# TC4plus.net
KiCad netlist of a schematic drawn in EAGLE
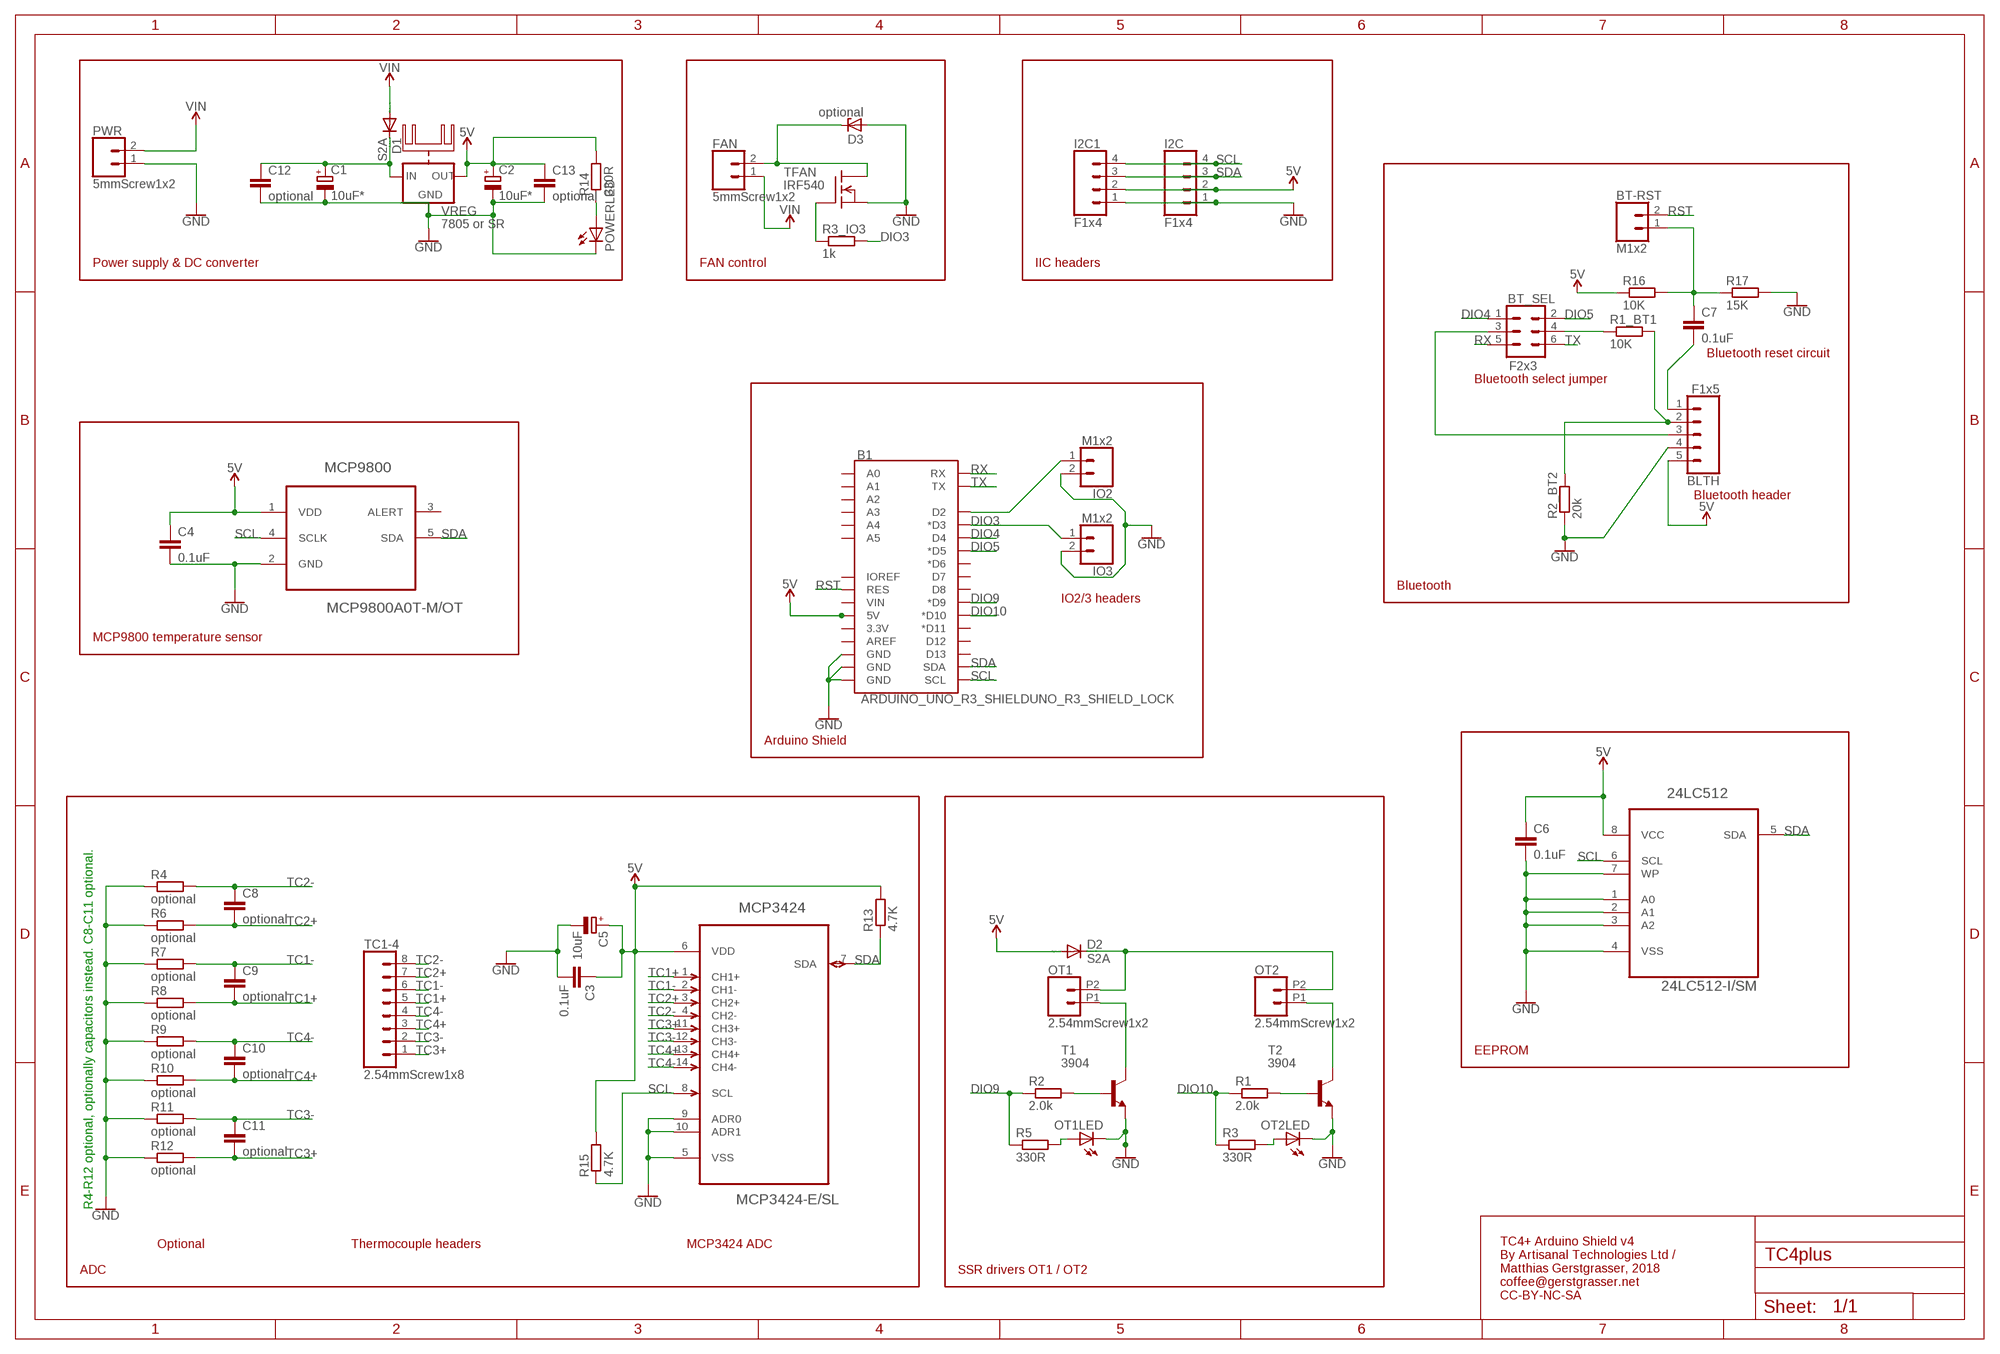
[diagram p0: schematic, sheet 1]

(export (version "E")
  (design (tool "Eeschema 10.0.6"))
  (components
    (comp (ref "24LC512")
      (value "24LC512-I/SM")
      (footprint "eagle-import:SOIC127P794X203-8N")
      (libsource (lib "eagle-import") (part "24LC512-I/SM"))
    )
    (comp (ref "B1")
      (value "ARDUINO_UNO_R3_SHIELDUNO_R3_SHIELD_LOCK")
      (footprint "eagle-import:UNO_R3_SHIELD_LOCK")
      (libsource (lib "eagle-import") (part "ARDUINO_UNO_R3_SHIELDUNO_R3_SHIELD_LOCK"))
    )
    (comp (ref "BLTH")
      (value "F1x5")
      (footprint "eagle-import:1X05_LOCK")
      (libsource (lib "eagle-import") (part "CONN_05LOCK"))
    )
    (comp (ref "BT-RST")
      (value "M1x2")
      (footprint "eagle-import:1X02")
      (libsource (lib "eagle-import") (part "CONN_02"))
    )
    (comp (ref "BT_SEL")
      (value "F2x3")
      (footprint "eagle-import:2X3")
      (libsource (lib "eagle-import") (part "CONN_03X2FEMALE"))
    )
    (comp (ref "C1")
      (value "10uF*")
      (footprint "eagle-import:E2-5")
      (libsource (lib "eagle-import") (part "CPOL-EUE2-5"))
    )
    (comp (ref "C2")
      (value "10uF*")
      (footprint "eagle-import:E2-5")
      (libsource (lib "eagle-import") (part "CPOL-EUE2-5"))
    )
    (comp (ref "C3")
      (value "0.1uF")
      (footprint "eagle-import:C0603")
      (libsource (lib "eagle-import") (part "C-EUC0603"))
    )
    (comp (ref "C4")
      (value "0.1uF")
      (footprint "eagle-import:C0603")
      (libsource (lib "eagle-import") (part "C-EUC0603"))
    )
    (comp (ref "C5")
      (value "10uF")
      (footprint "eagle-import:A_3216-18R")
      (libsource (lib "eagle-import") (part "CPOL-EUA/3216-18R"))
    )
    (comp (ref "C6")
      (value "0.1uF")
      (footprint "eagle-import:C0603")
      (libsource (lib "eagle-import") (part "C-EUC0603"))
    )
    (comp (ref "C7")
      (value "0.1uF")
      (footprint "eagle-import:C0603")
      (libsource (lib "eagle-import") (part "C-EUC0603"))
    )
    (comp (ref "C8")
      (value "optional")
      (footprint "eagle-import:C0603")
      (libsource (lib "eagle-import") (part "C-EUC0603"))
    )
    (comp (ref "C9")
      (value "optional")
      (footprint "eagle-import:C0603")
      (libsource (lib "eagle-import") (part "C-EUC0603"))
    )
    (comp (ref "C10")
      (value "optional")
      (footprint "eagle-import:C0603")
      (libsource (lib "eagle-import") (part "C-EUC0603"))
    )
    (comp (ref "C11")
      (value "optional")
      (footprint "eagle-import:C0603")
      (libsource (lib "eagle-import") (part "C-EUC0603"))
    )
    (comp (ref "C12")
      (value "optional")
      (footprint "eagle-import:C025-025X050")
      (libsource (lib "eagle-import") (part "C-EU025-025X050"))
    )
    (comp (ref "C13")
      (value "optional")
      (footprint "eagle-import:C025-025X050")
      (libsource (lib "eagle-import") (part "C-EU025-025X050"))
    )
    (comp (ref "D1")
      (value "S2A")
      (footprint "eagle-import:DO214AA")
      (libsource (lib "eagle-import") (part "DIODE-DO214AA"))
    )
    (comp (ref "D2")
      (value "S2A")
      (footprint "eagle-import:DO214AA")
      (libsource (lib "eagle-import") (part "DIODE-DO214AA"))
    )
    (comp (ref "D3")
      (value "optional")
      (footprint "eagle-import:SMB")
      (libsource (lib "eagle-import") (part "ZENER-DIODESMB"))
    )
    (comp (ref "FAN")
      (value "5mmScrew1x2")
      (footprint "eagle-import:SCREWTERMINAL-5MM-2")
      (libsource (lib "eagle-import") (part "SparkFun-Connectors_513_CONN_025MM"))
    )
    (comp (ref "I2C")
      (value "F1x4")
      (footprint "eagle-import:1X04_LOCK")
      (libsource (lib "eagle-import") (part "CONN_04LOCK"))
    )
    (comp (ref "I2C1")
      (value "F1x4")
      (footprint "eagle-import:1X04_LOCK")
      (libsource (lib "eagle-import") (part "CONN_04LOCK"))
    )
    (comp (ref "IO2")
      (value "M1x2")
      (footprint "eagle-import:1X02")
      (libsource (lib "eagle-import") (part "CONN_02"))
    )
    (comp (ref "IO3")
      (value "M1x2")
      (footprint "eagle-import:1X02")
      (libsource (lib "eagle-import") (part "CONN_02"))
    )
    (comp (ref "MCP3424")
      (value "MCP3424-E/SL")
      (footprint "eagle-import:SOIC127P600X175-14N")
      (libsource (lib "eagle-import") (part "MCP3424-E/SL"))
    )
    (comp (ref "MCP9800")
      (value "MCP9800A0T-M/OT")
      (footprint "eagle-import:SOT95P280X145-5N")
      (libsource (lib "eagle-import") (part "MCP9800A0T-M/OT"))
    )
    (comp (ref "OT1")
      (value "2.54mmScrew1x2")
      (footprint "eagle-import:1X02_2.54_SCREWTERM")
      (libsource (lib "eagle-import") (part "SparkFun-Connectors_513_CONN_022.54MM_SCREWTERM"))
    )
    (comp (ref "OT1LED")
      (value "LEDCHIP-LED0603")
      (footprint "eagle-import:CHIP-LED0603")
      (libsource (lib "eagle-import") (part "LEDCHIP-LED0603"))
    )
    (comp (ref "OT2")
      (value "2.54mmScrew1x2")
      (footprint "eagle-import:1X02_2.54_SCREWTERM")
      (libsource (lib "eagle-import") (part "SparkFun-Connectors_513_CONN_022.54MM_SCREWTERM"))
    )
    (comp (ref "OT2LED")
      (value "LEDCHIP-LED0603")
      (footprint "eagle-import:CHIP-LED0603")
      (libsource (lib "eagle-import") (part "LEDCHIP-LED0603"))
    )
    (comp (ref "POWERLED")
      (value "LEDCHIP-LED0603")
      (footprint "eagle-import:CHIP-LED0603")
      (libsource (lib "eagle-import") (part "LEDCHIP-LED0603"))
    )
    (comp (ref "PWR")
      (value "5mmScrew1x2")
      (footprint "eagle-import:SCREWTERMINAL-5MM-2")
      (libsource (lib "eagle-import") (part "SparkFun-Connectors_513_CONN_025MM"))
    )
    (comp (ref "R1")
      (value "2.0k")
      (footprint "eagle-import:R0603")
      (libsource (lib "eagle-import") (part "R-EU_R0603"))
    )
    (comp (ref "R1_BT1")
      (value "10K")
      (footprint "eagle-import:R0603")
      (libsource (lib "eagle-import") (part "R-EU_R0603"))
    )
    (comp (ref "R2")
      (value "2.0k")
      (footprint "eagle-import:R0603")
      (libsource (lib "eagle-import") (part "R-EU_R0603"))
    )
    (comp (ref "R2_BT2")
      (value "20k")
      (footprint "eagle-import:R0603")
      (libsource (lib "eagle-import") (part "R-EU_R0603"))
    )
    (comp (ref "R3")
      (value "330R")
      (footprint "eagle-import:R0603")
      (libsource (lib "eagle-import") (part "R-EU_R0603"))
    )
    (comp (ref "R3_IO3")
      (value "1k")
      (footprint "eagle-import:R0603")
      (libsource (lib "eagle-import") (part "R-EU_R0603"))
    )
    (comp (ref "R4")
      (value "optional")
      (footprint "eagle-import:R0603")
      (libsource (lib "eagle-import") (part "R-EU_R0603"))
    )
    (comp (ref "R5")
      (value "330R")
      (footprint "eagle-import:R0603")
      (libsource (lib "eagle-import") (part "R-EU_R0603"))
    )
    (comp (ref "R6")
      (value "optional")
      (footprint "eagle-import:R0603")
      (libsource (lib "eagle-import") (part "R-EU_R0603"))
    )
    (comp (ref "R7")
      (value "optional")
      (footprint "eagle-import:R0603")
      (libsource (lib "eagle-import") (part "R-EU_R0603"))
    )
    (comp (ref "R8")
      (value "optional")
      (footprint "eagle-import:R0603")
      (libsource (lib "eagle-import") (part "R-EU_R0603"))
    )
    (comp (ref "R9")
      (value "optional")
      (footprint "eagle-import:R0603")
      (libsource (lib "eagle-import") (part "R-EU_R0603"))
    )
    (comp (ref "R10")
      (value "optional")
      (footprint "eagle-import:R0603")
      (libsource (lib "eagle-import") (part "R-EU_R0603"))
    )
    (comp (ref "R11")
      (value "optional")
      (footprint "eagle-import:R0603")
      (libsource (lib "eagle-import") (part "R-EU_R0603"))
    )
    (comp (ref "R12")
      (value "optional")
      (footprint "eagle-import:R0603")
      (libsource (lib "eagle-import") (part "R-EU_R0603"))
    )
    (comp (ref "R13")
      (value "4.7K")
      (footprint "eagle-import:R0603")
      (libsource (lib "eagle-import") (part "R-EU_R0603"))
    )
    (comp (ref "R14")
      (value "330R")
      (footprint "eagle-import:R0603")
      (libsource (lib "eagle-import") (part "R-EU_R0603"))
    )
    (comp (ref "R15")
      (value "4.7K")
      (footprint "eagle-import:R0603")
      (libsource (lib "eagle-import") (part "R-EU_R0603"))
    )
    (comp (ref "R16")
      (value "10K")
      (footprint "eagle-import:R0603")
      (libsource (lib "eagle-import") (part "R-EU_R0603"))
    )
    (comp (ref "R17")
      (value "15K")
      (footprint "eagle-import:R0603")
      (libsource (lib "eagle-import") (part "R-EU_R0603"))
    )
    (comp (ref "T1")
      (value "3904")
      (footprint "eagle-import:SOT23-BEC")
      (libsource (lib "eagle-import") (part "-NPN-SOT23-BECMMBT3904LT1"))
    )
    (comp (ref "T2")
      (value "3904")
      (footprint "eagle-import:SOT23-BEC")
      (libsource (lib "eagle-import") (part "-NPN-SOT23-BECMMBT3904LT1"))
    )
    (comp (ref "TC1-4")
      (value "2.54mmScrew1x8")
      (footprint "eagle-import:1X08")
      (libsource (lib "eagle-import") (part "CONN_08{dblquote}"))
    )
    (comp (ref "TFAN")
      (value "IRF540")
      (footprint "eagle-import:TO220")
      (libsource (lib "eagle-import") (part "IRF540"))
    )
    (comp (ref "VREG")
      (value "7805 or SR")
      (footprint "eagle-import:78XXH")
      (libsource (lib "eagle-import") (part "78XXH"))
    )
  )
  (nets
    (net (code "1") (name "/DIO3") (class "Default")
      (node (ref "B1") (pin "D3") (pinfunction "*D3_D3") (pintype "bidirectional"))
      (node (ref "IO3") (pin "1") (pinfunction "1_1") (pintype "passive"))
      (node (ref "R3_IO3") (pin "2") (pinfunction "2_2") (pintype "passive"))
    )
    (net (code "2") (name "/DIO4") (class "Default")
      (node (ref "B1") (pin "D4") (pinfunction "D4_D4") (pintype "bidirectional"))
      (node (ref "BT_SEL") (pin "1") (pinfunction "1_1") (pintype "bidirectional"))
    )
    (net (code "3") (name "/DIO5") (class "Default")
      (node (ref "B1") (pin "D5") (pinfunction "*D5_D5") (pintype "bidirectional"))
      (node (ref "BT_SEL") (pin "2") (pinfunction "2_2") (pintype "bidirectional"))
    )
    (net (code "4") (name "/DIO9") (class "Default")
      (node (ref "B1") (pin "D9") (pinfunction "*D9_D9") (pintype "bidirectional"))
      (node (ref "R2") (pin "1") (pinfunction "1_1") (pintype "passive"))
      (node (ref "R5") (pin "1") (pinfunction "1_1") (pintype "passive"))
    )
    (net (code "5") (name "/DIO10") (class "Default")
      (node (ref "B1") (pin "D10") (pinfunction "*D10_D10") (pintype "bidirectional"))
      (node (ref "R1") (pin "1") (pinfunction "1_1") (pintype "passive"))
      (node (ref "R3") (pin "1") (pinfunction "1_1") (pintype "passive"))
    )
    (net (code "6") (name "/RST") (class "Default")
      (node (ref "B1") (pin "RES") (pinfunction "RES_RES") (pintype "bidirectional"))
      (node (ref "BT-RST") (pin "2") (pinfunction "2_2") (pintype "passive"))
    )
    (net (code "7") (name "/RX") (class "Default")
      (node (ref "B1") (pin "RX") (pinfunction "RX_RX") (pintype "bidirectional"))
      (node (ref "BT_SEL") (pin "5") (pinfunction "5_5") (pintype "bidirectional"))
    )
    (net (code "8") (name "/SCL") (class "Default")
      (node (ref "24LC512") (pin "6") (pinfunction "SCL_6") (pintype "input"))
      (node (ref "B1") (pin "SCL") (pinfunction "SCL_SCL") (pintype "bidirectional"))
      (node (ref "I2C") (pin "4") (pinfunction "4_4") (pintype "passive"))
      (node (ref "I2C1") (pin "4") (pinfunction "4_4") (pintype "passive"))
      (node (ref "MCP3424") (pin "8") (pinfunction "SCL_8") (pintype "input"))
      (node (ref "MCP9800") (pin "4") (pinfunction "SCLK_4") (pintype "input"))
      (node (ref "R15") (pin "1") (pinfunction "1_1") (pintype "passive"))
    )
    (net (code "9") (name "/SDA") (class "Default")
      (node (ref "24LC512") (pin "5") (pinfunction "SDA_5") (pintype "bidirectional"))
      (node (ref "B1") (pin "SDA") (pinfunction "SDA_SDA") (pintype "bidirectional"))
      (node (ref "I2C") (pin "3") (pinfunction "3_3") (pintype "passive"))
      (node (ref "I2C1") (pin "3") (pinfunction "3_3") (pintype "passive"))
      (node (ref "MCP3424") (pin "7") (pinfunction "SDA_7") (pintype "bidirectional"))
      (node (ref "MCP9800") (pin "5") (pinfunction "SDA_5") (pintype "bidirectional"))
      (node (ref "R13") (pin "1") (pinfunction "1_1") (pintype "passive"))
    )
    (net (code "10") (name "/TC1+") (class "Default")
      (node (ref "C9") (pin "2") (pinfunction "2_2") (pintype "passive"))
      (node (ref "MCP3424") (pin "1") (pinfunction "CH1+_1") (pintype "input"))
      (node (ref "R8") (pin "2") (pinfunction "2_2") (pintype "passive"))
      (node (ref "TC1-4") (pin "5") (pinfunction "5_5") (pintype "passive"))
    )
    (net (code "11") (name "/TC1-") (class "Default")
      (node (ref "C9") (pin "1") (pinfunction "1_1") (pintype "passive"))
      (node (ref "MCP3424") (pin "2") (pinfunction "CH1-_2") (pintype "input"))
      (node (ref "R7") (pin "2") (pinfunction "2_2") (pintype "passive"))
      (node (ref "TC1-4") (pin "6") (pinfunction "6_6") (pintype "passive"))
    )
    (net (code "12") (name "/TC2+") (class "Default")
      (node (ref "C8") (pin "2") (pinfunction "2_2") (pintype "passive"))
      (node (ref "MCP3424") (pin "3") (pinfunction "CH2+_3") (pintype "input"))
      (node (ref "R6") (pin "2") (pinfunction "2_2") (pintype "passive"))
      (node (ref "TC1-4") (pin "7") (pinfunction "7_7") (pintype "passive"))
    )
    (net (code "13") (name "/TC2-") (class "Default")
      (node (ref "C8") (pin "1") (pinfunction "1_1") (pintype "passive"))
      (node (ref "MCP3424") (pin "4") (pinfunction "CH2-_4") (pintype "input"))
      (node (ref "R4") (pin "2") (pinfunction "2_2") (pintype "passive"))
      (node (ref "TC1-4") (pin "8") (pinfunction "8_8") (pintype "passive"))
    )
    (net (code "14") (name "/TC3+") (class "Default")
      (node (ref "C11") (pin "2") (pinfunction "2_2") (pintype "passive"))
      (node (ref "MCP3424") (pin "11") (pinfunction "CH3+_11") (pintype "input"))
      (node (ref "R12") (pin "2") (pinfunction "2_2") (pintype "passive"))
      (node (ref "TC1-4") (pin "1") (pinfunction "1_1") (pintype "passive"))
    )
    (net (code "15") (name "/TC3-") (class "Default")
      (node (ref "C11") (pin "1") (pinfunction "1_1") (pintype "passive"))
      (node (ref "MCP3424") (pin "12") (pinfunction "CH3-_12") (pintype "input"))
      (node (ref "R11") (pin "2") (pinfunction "2_2") (pintype "passive"))
      (node (ref "TC1-4") (pin "2") (pinfunction "2_2") (pintype "passive"))
    )
    (net (code "16") (name "/TC4+") (class "Default")
      (node (ref "C10") (pin "2") (pinfunction "2_2") (pintype "passive"))
      (node (ref "MCP3424") (pin "13") (pinfunction "CH4+_13") (pintype "input"))
      (node (ref "R10") (pin "2") (pinfunction "2_2") (pintype "passive"))
      (node (ref "TC1-4") (pin "3") (pinfunction "3_3") (pintype "passive"))
    )
    (net (code "17") (name "/TC4-") (class "Default")
      (node (ref "C10") (pin "1") (pinfunction "1_1") (pintype "passive"))
      (node (ref "MCP3424") (pin "14") (pinfunction "CH4-_14") (pintype "input"))
      (node (ref "R9") (pin "2") (pinfunction "2_2") (pintype "passive"))
      (node (ref "TC1-4") (pin "4") (pinfunction "4_4") (pintype "passive"))
    )
    (net (code "18") (name "/TX") (class "Default")
      (node (ref "B1") (pin "TX") (pinfunction "TX_TX") (pintype "bidirectional"))
      (node (ref "BT_SEL") (pin "6") (pinfunction "6_6") (pintype "bidirectional"))
    )
    (net (code "19") (name "5V") (class "Default")
      (node (ref "24LC512") (pin "8") (pinfunction "VCC_8") (pintype "power_in"))
      (node (ref "B1") (pin "5V") (pinfunction "5V_5V") (pintype "bidirectional"))
      (node (ref "BLTH") (pin "5") (pinfunction "5_5") (pintype "passive"))
      (node (ref "C13") (pin "1") (pinfunction "1_1") (pintype "passive"))
      (node (ref "C2") (pin "+") (pinfunction "+_+") (pintype "passive"))
      (node (ref "C3") (pin "1") (pinfunction "1_1") (pintype "passive"))
      (node (ref "C4") (pin "1") (pinfunction "1_1") (pintype "passive"))
      (node (ref "C5") (pin "+") (pinfunction "+_+") (pintype "passive"))
      (node (ref "C6") (pin "1") (pinfunction "1_1") (pintype "passive"))
      (node (ref "D2") (pin "A") (pinfunction "A_A") (pintype "passive"))
      (node (ref "I2C") (pin "2") (pinfunction "2_2") (pintype "passive"))
      (node (ref "I2C1") (pin "2") (pinfunction "2_2") (pintype "passive"))
      (node (ref "MCP3424") (pin "6") (pinfunction "VDD_6") (pintype "power_in"))
      (node (ref "MCP9800") (pin "1") (pinfunction "VDD_1") (pintype "power_in"))
      (node (ref "R13") (pin "2") (pinfunction "2_2") (pintype "passive"))
      (node (ref "R14") (pin "2") (pinfunction "2_2") (pintype "passive"))
      (node (ref "R15") (pin "2") (pinfunction "2_2") (pintype "passive"))
      (node (ref "R16") (pin "1") (pinfunction "1_1") (pintype "passive"))
      (node (ref "VREG") (pin "OUT") (pinfunction "OUT_OUT") (pintype "passive"))
    )
    (net (code "20") (name "GND") (class "Default")
      (node (ref "24LC512") (pin "1") (pinfunction "A0_1") (pintype "input"))
      (node (ref "24LC512") (pin "2") (pinfunction "A1_2") (pintype "input"))
      (node (ref "24LC512") (pin "3") (pinfunction "A2_3") (pintype "input"))
      (node (ref "24LC512") (pin "4") (pinfunction "VSS_4") (pintype "passive"))
      (node (ref "24LC512") (pin "7") (pinfunction "WP_7") (pintype "input"))
      (node (ref "B1") (pin "GND@0") (pinfunction "GND_GND@0") (pintype "bidirectional"))
      (node (ref "B1") (pin "GND@1") (pinfunction "GND_GND@1") (pintype "bidirectional"))
      (node (ref "B1") (pin "GND@2") (pinfunction "GND_GND@2") (pintype "bidirectional"))
      (node (ref "BLTH") (pin "4") (pinfunction "4_4") (pintype "passive"))
      (node (ref "C1") (pin "-") (pinfunction "-_-") (pintype "passive"))
      (node (ref "C12") (pin "2") (pinfunction "2_2") (pintype "passive"))
      (node (ref "C13") (pin "2") (pinfunction "2_2") (pintype "passive"))
      (node (ref "C2") (pin "-") (pinfunction "-_-") (pintype "passive"))
      (node (ref "C3") (pin "2") (pinfunction "2_2") (pintype "passive"))
      (node (ref "C4") (pin "2") (pinfunction "2_2") (pintype "passive"))
      (node (ref "C5") (pin "-") (pinfunction "-_-") (pintype "passive"))
      (node (ref "C6") (pin "2") (pinfunction "2_2") (pintype "passive"))
      (node (ref "D3") (pin "A") (pinfunction "A_A") (pintype "passive"))
      (node (ref "I2C") (pin "1") (pinfunction "1_1") (pintype "passive"))
      (node (ref "I2C1") (pin "1") (pinfunction "1_1") (pintype "passive"))
      (node (ref "IO2") (pin "2") (pinfunction "2_2") (pintype "passive"))
      (node (ref "IO3") (pin "2") (pinfunction "2_2") (pintype "passive"))
      (node (ref "MCP3424") (pin "10") (pinfunction "ADR1_10") (pintype "input"))
      (node (ref "MCP3424") (pin "5") (pinfunction "VSS_5") (pintype "power_in"))
      (node (ref "MCP3424") (pin "9") (pinfunction "ADR0_9") (pintype "input"))
      (node (ref "MCP9800") (pin "2") (pinfunction "GND_2") (pintype "passive"))
      (node (ref "OT1LED") (pin "C") (pinfunction "C_C") (pintype "passive"))
      (node (ref "OT2LED") (pin "C") (pinfunction "C_C") (pintype "passive"))
      (node (ref "POWERLED") (pin "C") (pinfunction "C_C") (pintype "passive"))
      (node (ref "PWR") (pin "1") (pinfunction "1_1") (pintype "passive"))
      (node (ref "R10") (pin "1") (pinfunction "1_1") (pintype "passive"))
      (node (ref "R11") (pin "1") (pinfunction "1_1") (pintype "passive"))
      (node (ref "R12") (pin "1") (pinfunction "1_1") (pintype "passive"))
      (node (ref "R17") (pin "2") (pinfunction "2_2") (pintype "passive"))
      (node (ref "R2_BT2") (pin "1") (pinfunction "1_1") (pintype "passive"))
      (node (ref "R4") (pin "1") (pinfunction "1_1") (pintype "passive"))
      (node (ref "R6") (pin "1") (pinfunction "1_1") (pintype "passive"))
      (node (ref "R7") (pin "1") (pinfunction "1_1") (pintype "passive"))
      (node (ref "R8") (pin "1") (pinfunction "1_1") (pintype "passive"))
      (node (ref "R9") (pin "1") (pinfunction "1_1") (pintype "passive"))
      (node (ref "T1") (pin "E") (pinfunction "E_E") (pintype "passive"))
      (node (ref "T2") (pin "E") (pinfunction "E_E") (pintype "passive"))
      (node (ref "TFAN") (pin "3") (pinfunction "S_3") (pintype "passive"))
      (node (ref "VREG") (pin "GND") (pinfunction "GND_GND") (pintype "input"))
    )
    (net (code "21") (name "Net-(B1-PadD2)") (class "Default")
      (node (ref "B1") (pin "D2") (pinfunction "D2_D2") (pintype "bidirectional"))
      (node (ref "IO2") (pin "1") (pinfunction "1_1") (pintype "passive"))
    )
    (net (code "22") (name "Net-(BLTH-Pad1)") (class "Default")
      (node (ref "BLTH") (pin "1") (pinfunction "1_1") (pintype "passive"))
      (node (ref "C7") (pin "2") (pinfunction "2_2") (pintype "passive"))
    )
    (net (code "23") (name "Net-(BLTH-Pad2)") (class "Default")
      (node (ref "BLTH") (pin "2") (pinfunction "2_2") (pintype "passive"))
      (node (ref "R1_BT1") (pin "2") (pinfunction "2_2") (pintype "passive"))
      (node (ref "R2_BT2") (pin "2") (pinfunction "2_2") (pintype "passive"))
    )
    (net (code "24") (name "Net-(BLTH-Pad3)") (class "Default")
      (node (ref "BLTH") (pin "3") (pinfunction "3_3") (pintype "passive"))
      (node (ref "BT_SEL") (pin "3") (pinfunction "3_3") (pintype "bidirectional"))
    )
    (net (code "25") (name "Net-(BT-RST-Pad1)") (class "Default")
      (node (ref "BT-RST") (pin "1") (pinfunction "1_1") (pintype "passive"))
      (node (ref "C7") (pin "1") (pinfunction "1_1") (pintype "passive"))
      (node (ref "R16") (pin "2") (pinfunction "2_2") (pintype "passive"))
      (node (ref "R17") (pin "1") (pinfunction "1_1") (pintype "passive"))
    )
    (net (code "26") (name "Net-(BT_SEL-Pad4)") (class "Default")
      (node (ref "BT_SEL") (pin "4") (pinfunction "4_4") (pintype "bidirectional"))
      (node (ref "R1_BT1") (pin "1") (pinfunction "1_1") (pintype "passive"))
    )
    (net (code "27") (name "Net-(C1-Pad+)") (class "Default")
      (node (ref "C1") (pin "+") (pinfunction "+_+") (pintype "passive"))
      (node (ref "C12") (pin "1") (pinfunction "1_1") (pintype "passive"))
      (node (ref "D1") (pin "C") (pinfunction "C_C") (pintype "passive"))
      (node (ref "VREG") (pin "IN") (pinfunction "IN_IN") (pintype "input"))
    )
    (net (code "28") (name "Net-(OT1-1)") (class "Default")
      (node (ref "OT1") (pin "P1") (pinfunction "1_P1") (pintype "passive"))
      (node (ref "T1") (pin "C") (pinfunction "C_C") (pintype "passive"))
    )
    (net (code "29") (name "Net-(OT1-2)") (class "Default")
      (node (ref "D2") (pin "C") (pinfunction "C_C") (pintype "passive"))
      (node (ref "OT1") (pin "P2") (pinfunction "2_P2") (pintype "passive"))
      (node (ref "OT2") (pin "P2") (pinfunction "2_P2") (pintype "passive"))
    )
    (net (code "30") (name "Net-(OT1LED-PadA)") (class "Default")
      (node (ref "OT1LED") (pin "A") (pinfunction "A_A") (pintype "passive"))
      (node (ref "R5") (pin "2") (pinfunction "2_2") (pintype "passive"))
    )
    (net (code "31") (name "Net-(OT2-1)") (class "Default")
      (node (ref "OT2") (pin "P1") (pinfunction "1_P1") (pintype "passive"))
      (node (ref "T2") (pin "C") (pinfunction "C_C") (pintype "passive"))
    )
    (net (code "32") (name "Net-(OT2LED-PadA)") (class "Default")
      (node (ref "OT2LED") (pin "A") (pinfunction "A_A") (pintype "passive"))
      (node (ref "R3") (pin "2") (pinfunction "2_2") (pintype "passive"))
    )
    (net (code "33") (name "Net-(POWERLED-PadA)") (class "Default")
      (node (ref "POWERLED") (pin "A") (pinfunction "A_A") (pintype "passive"))
      (node (ref "R14") (pin "1") (pinfunction "1_1") (pintype "passive"))
    )
    (net (code "34") (name "Net-(R1-Pad2)") (class "Default")
      (node (ref "R1") (pin "2") (pinfunction "2_2") (pintype "passive"))
      (node (ref "T2") (pin "B") (pinfunction "B_B") (pintype "passive"))
    )
    (net (code "35") (name "Net-(R2-Pad2)") (class "Default")
      (node (ref "R2") (pin "2") (pinfunction "2_2") (pintype "passive"))
      (node (ref "T1") (pin "B") (pinfunction "B_B") (pintype "passive"))
    )
    (net (code "36") (name "Net-(TFAN-D)") (class "Default")
      (node (ref "D3") (pin "C") (pinfunction "C_C") (pintype "passive"))
      (node (ref "FAN") (pin "2") (pinfunction "2_2") (pintype "passive"))
      (node (ref "TFAN") (pin "2") (pinfunction "D_2") (pintype "passive"))
    )
    (net (code "37") (name "Net-(TFAN-G)") (class "Default")
      (node (ref "R3_IO3") (pin "1") (pinfunction "1_1") (pintype "passive"))
      (node (ref "TFAN") (pin "1") (pinfunction "G_1") (pintype "passive"))
    )
    (net (code "38") (name "VIN") (class "Default")
      (node (ref "D1") (pin "A") (pinfunction "A_A") (pintype "passive"))
      (node (ref "FAN") (pin "1") (pinfunction "1_1") (pintype "passive"))
      (node (ref "PWR") (pin "2") (pinfunction "2_2") (pintype "passive"))
    )
    (net (code "39") (name "unconnected-(B1-*D6-PadD6)") (class "Default")
      (node (ref "B1") (pin "D6") (pinfunction "*D6_D6") (pintype "bidirectional"))
    )
    (net (code "40") (name "unconnected-(B1-*D11-PadD11)") (class "Default")
      (node (ref "B1") (pin "D11") (pinfunction "*D11_D11") (pintype "bidirectional"))
    )
    (net (code "41") (name "unconnected-(B1-Pad3.3V)") (class "Default")
      (node (ref "B1") (pin "3.3V") (pinfunction "3.3V_3.3V") (pintype "bidirectional"))
    )
    (net (code "42") (name "unconnected-(B1-PadA0)") (class "Default")
      (node (ref "B1") (pin "A0") (pinfunction "A0_A0") (pintype "bidirectional"))
    )
    (net (code "43") (name "unconnected-(B1-PadA1)") (class "Default")
      (node (ref "B1") (pin "A1") (pinfunction "A1_A1") (pintype "bidirectional"))
    )
    (net (code "44") (name "unconnected-(B1-PadA2)") (class "Default")
      (node (ref "B1") (pin "A2") (pinfunction "A2_A2") (pintype "bidirectional"))
    )
    (net (code "45") (name "unconnected-(B1-PadA3)") (class "Default")
      (node (ref "B1") (pin "A3") (pinfunction "A3_A3") (pintype "bidirectional"))
    )
    (net (code "46") (name "unconnected-(B1-PadA4)") (class "Default")
      (node (ref "B1") (pin "A4") (pinfunction "A4_A4") (pintype "bidirectional"))
    )
    (net (code "47") (name "unconnected-(B1-PadA5)") (class "Default")
      (node (ref "B1") (pin "A5") (pinfunction "A5_A5") (pintype "bidirectional"))
    )
    (net (code "48") (name "unconnected-(B1-PadAREF)") (class "Default")
      (node (ref "B1") (pin "AREF") (pinfunction "AREF_AREF") (pintype "bidirectional"))
    )
    (net (code "49") (name "unconnected-(B1-PadD7)") (class "Default")
      (node (ref "B1") (pin "D7") (pinfunction "D7_D7") (pintype "bidirectional"))
    )
    (net (code "50") (name "unconnected-(B1-PadD8)") (class "Default")
      (node (ref "B1") (pin "D8") (pinfunction "D8_D8") (pintype "bidirectional"))
    )
    (net (code "51") (name "unconnected-(B1-PadD12)") (class "Default")
      (node (ref "B1") (pin "D12") (pinfunction "D12_D12") (pintype "bidirectional"))
    )
    (net (code "52") (name "unconnected-(B1-PadD13)") (class "Default")
      (node (ref "B1") (pin "D13") (pinfunction "D13_D13") (pintype "bidirectional"))
    )
    (net (code "53") (name "unconnected-(B1-PadIOREF)") (class "Default")
      (node (ref "B1") (pin "IOREF") (pinfunction "IOREF_IOREF") (pintype "bidirectional"))
    )
    (net (code "54") (name "unconnected-(B1-PadVIN)") (class "Default")
      (node (ref "B1") (pin "VIN") (pinfunction "VIN_VIN") (pintype "bidirectional"))
    )
    (net (code "55") (name "unconnected-(MCP9800-ALERT-Pad3)") (class "Default")
      (node (ref "MCP9800") (pin "3") (pinfunction "ALERT_3") (pintype "output"))
    )
  )
)
